# WaterLevelControl.net
KiCad netlist of a schematic drawn in EAGLE
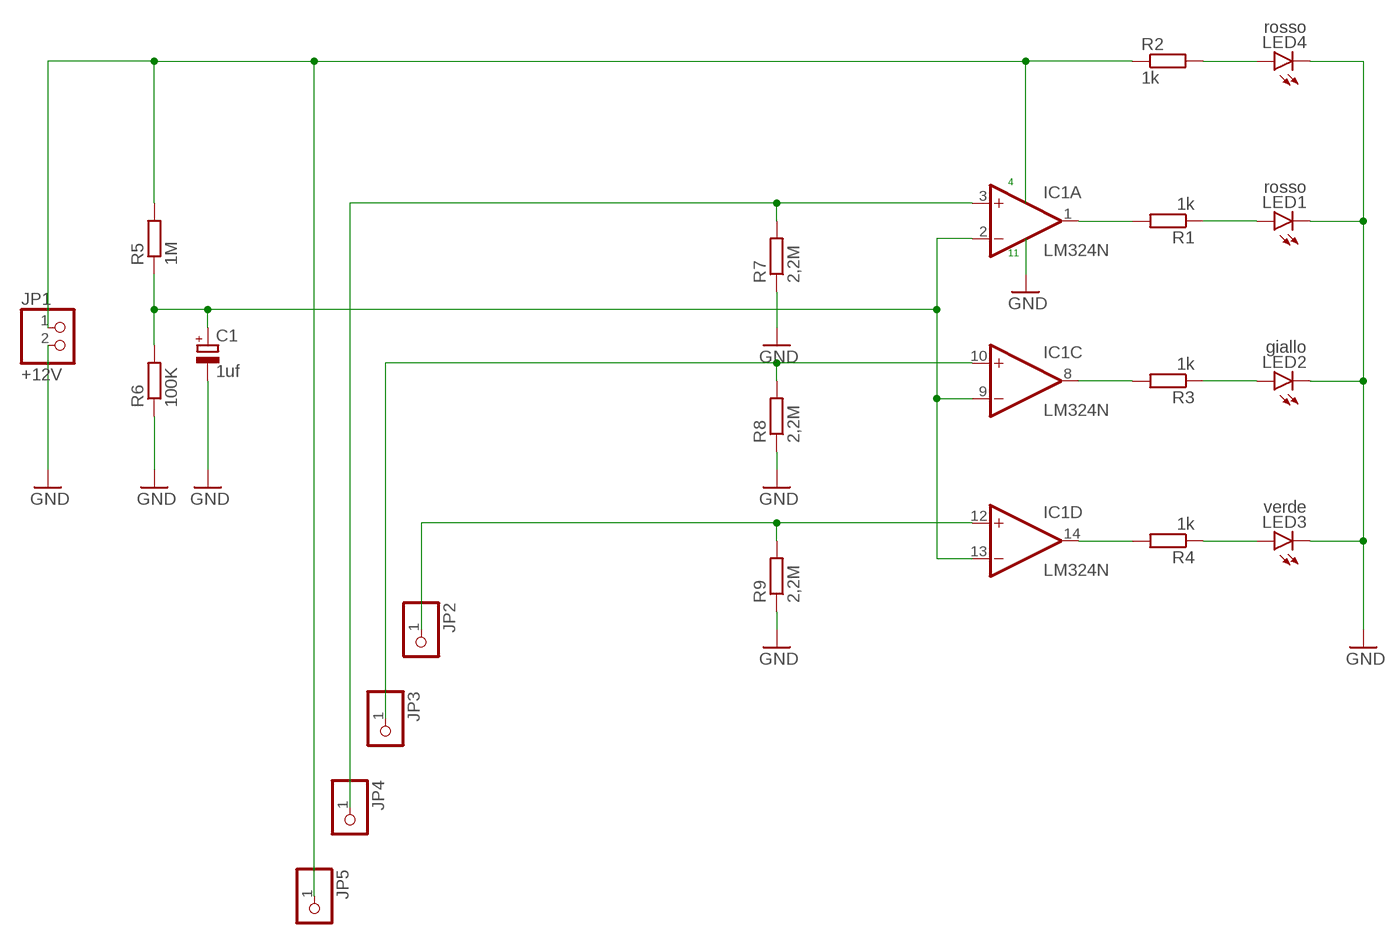
[diagram p0: schematic, sheet 1]

(export (version "E")
  (design (tool "Eeschema 10.0.6"))
  (components
    (comp (ref "C1")
      (value "1uf")
      (footprint "eagle-import:E2,5-5")
      (libsource (lib "eagle-import") (part "CPOL-EUE2.5-5"))
    )
    (comp (ref "IC1")
      (value "LM324N")
      (footprint "eagle-import:DIL14")
      (libsource (lib "eagle-import") (part "LM324N"))
    )
    (comp (ref "JP1")
      (value "+12V")
      (footprint "eagle-import:1X02")
      (libsource (lib "eagle-import") (part "PINHD-1X2"))
    )
    (comp (ref "JP2")
      (value "PINHD-1X1")
      (footprint "eagle-import:1X01")
      (libsource (lib "eagle-import") (part "PINHD-1X1"))
    )
    (comp (ref "JP3")
      (value "PINHD-1X1")
      (footprint "eagle-import:1X01")
      (libsource (lib "eagle-import") (part "PINHD-1X1"))
    )
    (comp (ref "JP4")
      (value "PINHD-1X1")
      (footprint "eagle-import:1X01")
      (libsource (lib "eagle-import") (part "PINHD-1X1"))
    )
    (comp (ref "JP5")
      (value "PINHD-1X1")
      (footprint "eagle-import:1X01")
      (libsource (lib "eagle-import") (part "PINHD-1X1"))
    )
    (comp (ref "LED1")
      (value "rosso")
      (footprint "eagle-import:LED3MM")
      (libsource (lib "eagle-import") (part "LED3MM"))
    )
    (comp (ref "LED2")
      (value "giallo")
      (footprint "eagle-import:LED3MM")
      (libsource (lib "eagle-import") (part "LED3MM"))
    )
    (comp (ref "LED3")
      (value "verde")
      (footprint "eagle-import:LED3MM")
      (libsource (lib "eagle-import") (part "LED3MM"))
    )
    (comp (ref "LED4")
      (value "rosso")
      (footprint "eagle-import:LED3MM")
      (libsource (lib "eagle-import") (part "LED3MM"))
    )
    (comp (ref "R1")
      (value "1k")
      (footprint "eagle-import:0207_10")
      (libsource (lib "eagle-import") (part "R-EU_0207/10"))
    )
    (comp (ref "R2")
      (value "1k")
      (footprint "eagle-import:0207_10")
      (libsource (lib "eagle-import") (part "R-EU_0207/10"))
    )
    (comp (ref "R3")
      (value "1k")
      (footprint "eagle-import:0207_10")
      (libsource (lib "eagle-import") (part "R-EU_0207/10"))
    )
    (comp (ref "R4")
      (value "1k")
      (footprint "eagle-import:0207_10")
      (libsource (lib "eagle-import") (part "R-EU_0207/10"))
    )
    (comp (ref "R5")
      (value "1M")
      (footprint "eagle-import:0207_10")
      (libsource (lib "eagle-import") (part "R-EU_0207/10"))
    )
    (comp (ref "R6")
      (value "100K")
      (footprint "eagle-import:0207_10")
      (libsource (lib "eagle-import") (part "R-EU_0207/10"))
    )
    (comp (ref "R7")
      (value "2,2M")
      (footprint "eagle-import:0207_10")
      (libsource (lib "eagle-import") (part "R-EU_0207/10"))
    )
    (comp (ref "R8")
      (value "2,2M")
      (footprint "eagle-import:0207_10")
      (libsource (lib "eagle-import") (part "R-EU_0207/10"))
    )
    (comp (ref "R9")
      (value "2,2M")
      (footprint "eagle-import:0207_10")
      (libsource (lib "eagle-import") (part "R-EU_0207/10"))
    )
  )
  (nets
    (net (code "1") (name "GND") (class "Default")
      (node (ref "C1") (pin "-") (pinfunction "-_-") (pintype "passive"))
      (node (ref "JP1") (pin "2") (pinfunction "2_2") (pintype "passive"))
      (node (ref "LED1") (pin "K") (pinfunction "C_K") (pintype "passive"))
      (node (ref "LED2") (pin "K") (pinfunction "C_K") (pintype "passive"))
      (node (ref "LED3") (pin "K") (pinfunction "C_K") (pintype "passive"))
      (node (ref "LED4") (pin "K") (pinfunction "C_K") (pintype "passive"))
      (node (ref "R6") (pin "1") (pinfunction "1_1") (pintype "passive"))
      (node (ref "R7") (pin "1") (pinfunction "1_1") (pintype "passive"))
      (node (ref "R8") (pin "1") (pinfunction "1_1") (pintype "passive"))
      (node (ref "R9") (pin "1") (pinfunction "1_1") (pintype "passive"))
    )
    (net (code "2") (name "Net-(IC1A-+IN)") (class "Default")
      (node (ref "IC1") (pin "3") (pinfunction "+IN_3") (pintype "input"))
      (node (ref "JP4") (pin "1") (pinfunction "1_1") (pintype "passive"))
      (node (ref "R7") (pin "2") (pinfunction "2_2") (pintype "passive"))
    )
    (net (code "3") (name "Net-(IC1A--IN)") (class "Default")
      (node (ref "C1") (pin "+") (pinfunction "+_+") (pintype "passive"))
      (node (ref "IC1") (pin "13") (pinfunction "-IN_13") (pintype "input"))
      (node (ref "IC1") (pin "2") (pinfunction "-IN_2") (pintype "input"))
      (node (ref "IC1") (pin "9") (pinfunction "-IN_9") (pintype "input"))
      (node (ref "R5") (pin "1") (pinfunction "1_1") (pintype "passive"))
      (node (ref "R6") (pin "2") (pinfunction "2_2") (pintype "passive"))
    )
    (net (code "4") (name "Net-(IC1A-OUT)") (class "Default")
      (node (ref "IC1") (pin "1") (pinfunction "OUT_1") (pintype "output"))
      (node (ref "R1") (pin "2") (pinfunction "2_2") (pintype "passive"))
    )
    (net (code "5") (name "Net-(IC1C-+IN)") (class "Default")
      (node (ref "IC1") (pin "10") (pinfunction "+IN_10") (pintype "input"))
      (node (ref "JP3") (pin "1") (pinfunction "1_1") (pintype "passive"))
      (node (ref "R8") (pin "2") (pinfunction "2_2") (pintype "passive"))
    )
    (net (code "6") (name "Net-(IC1C-OUT)") (class "Default")
      (node (ref "IC1") (pin "8") (pinfunction "OUT_8") (pintype "output"))
      (node (ref "R3") (pin "2") (pinfunction "2_2") (pintype "passive"))
    )
    (net (code "7") (name "Net-(IC1D-+IN)") (class "Default")
      (node (ref "IC1") (pin "12") (pinfunction "+IN_12") (pintype "input"))
      (node (ref "JP2") (pin "1") (pinfunction "1_1") (pintype "passive"))
      (node (ref "R9") (pin "2") (pinfunction "2_2") (pintype "passive"))
    )
    (net (code "8") (name "Net-(IC1D-OUT)") (class "Default")
      (node (ref "IC1") (pin "14") (pinfunction "OUT_14") (pintype "output"))
      (node (ref "R4") (pin "2") (pinfunction "2_2") (pintype "passive"))
    )
    (net (code "9") (name "Net-(JP1-Pad1)") (class "Default")
      (node (ref "JP1") (pin "1") (pinfunction "1_1") (pintype "passive"))
      (node (ref "JP5") (pin "1") (pinfunction "1_1") (pintype "passive"))
      (node (ref "R2") (pin "1") (pinfunction "1_1") (pintype "passive"))
      (node (ref "R5") (pin "2") (pinfunction "2_2") (pintype "passive"))
    )
    (net (code "10") (name "Net-(LED1-PadA)") (class "Default")
      (node (ref "LED1") (pin "A") (pinfunction "A_A") (pintype "passive"))
      (node (ref "R1") (pin "1") (pinfunction "1_1") (pintype "passive"))
    )
    (net (code "11") (name "Net-(LED2-PadA)") (class "Default")
      (node (ref "LED2") (pin "A") (pinfunction "A_A") (pintype "passive"))
      (node (ref "R3") (pin "1") (pinfunction "1_1") (pintype "passive"))
    )
    (net (code "12") (name "Net-(LED3-PadA)") (class "Default")
      (node (ref "LED3") (pin "A") (pinfunction "A_A") (pintype "passive"))
      (node (ref "R4") (pin "1") (pinfunction "1_1") (pintype "passive"))
    )
    (net (code "13") (name "Net-(LED4-PadA)") (class "Default")
      (node (ref "LED4") (pin "A") (pinfunction "A_A") (pintype "passive"))
      (node (ref "R2") (pin "2") (pinfunction "2_2") (pintype "passive"))
    )
  )
)
